# battery-charging.net
KiCad netlist of a schematic drawn in Altium Designer
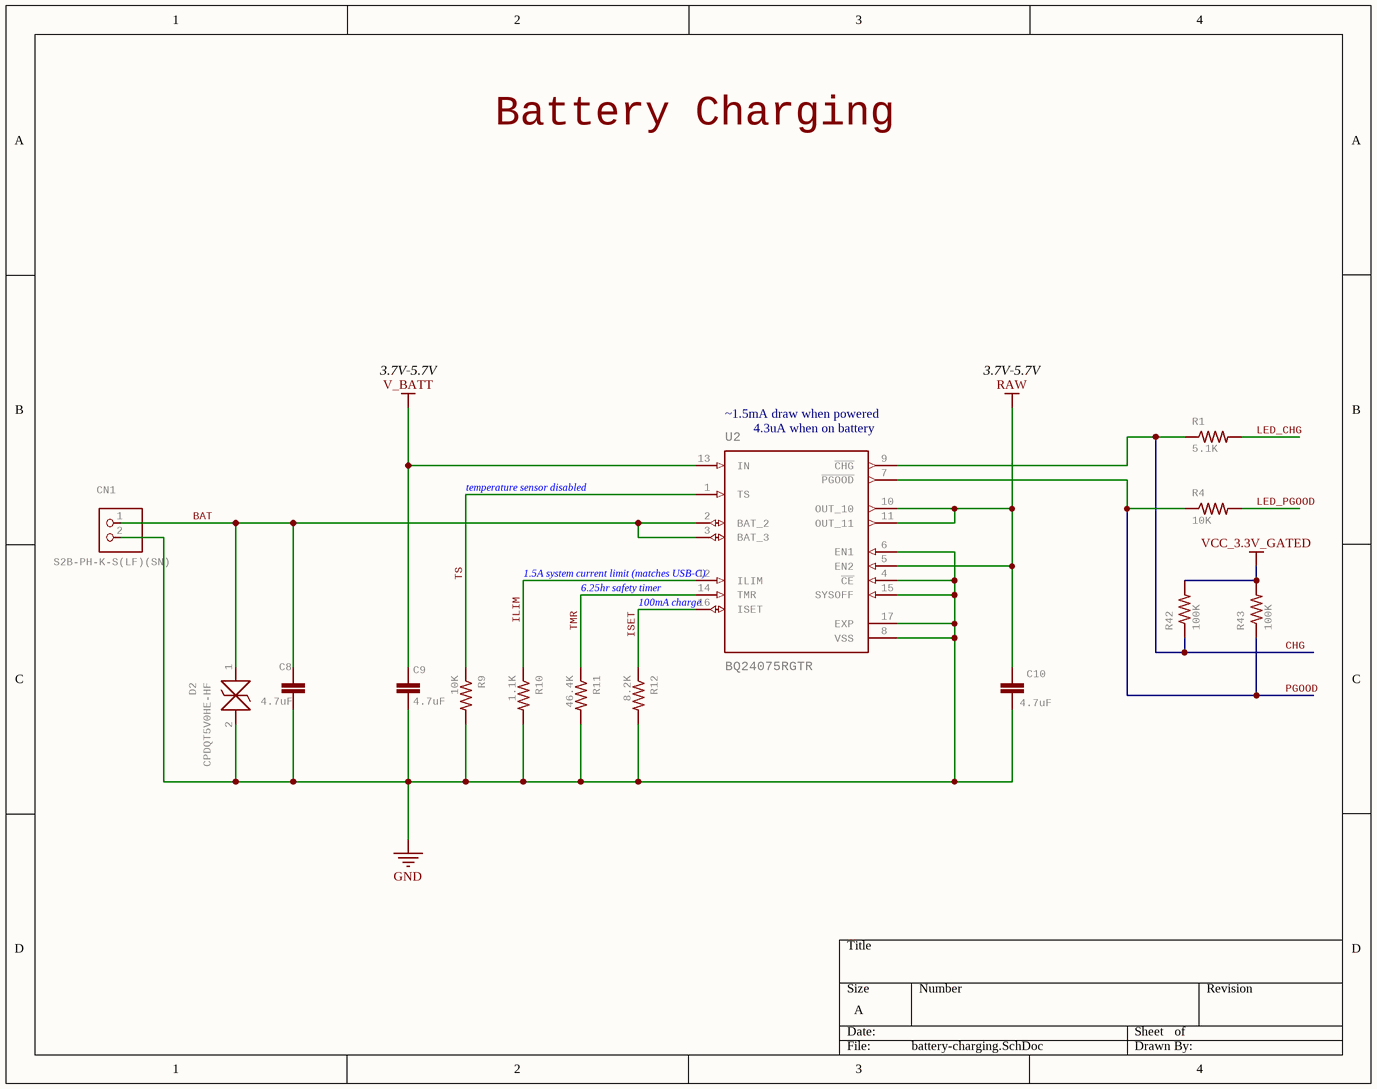
[diagram p0: battery-charging.SchDoc]

(export (version "E")
  (design (tool "Eeschema 10.0.6"))
  (components
    (comp (ref "C8")
      (value "4.7uF")
      (footprint "0402-CAP")
      (description "CapacitorStandard 0603 ceramic capacitor, and 0.1\" leaded capacitor.")
      (fields (field (name "MPN") "JMK105BBJ475MV-F"))
      (libsource (lib "rt10") (part "CAP0402-CAP"))
    )
    (comp (ref "C9")
      (value "4.7uF")
      (footprint "0402-CAP")
      (description "CapacitorStandard 0603 ceramic capacitor, and 0.1\" leaded capacitor.")
      (fields (field (name "MPN") "JMK105BBJ475MV-F"))
      (libsource (lib "rt10") (part "CAP0402-CAP"))
    )
    (comp (ref "C10")
      (value "4.7uF")
      (footprint "0402-CAP")
      (description "CapacitorStandard 0603 ceramic capacitor, and 0.1\" leaded capacitor.")
      (fields (field (name "MPN") "JMK105BBJ475MV-F"))
      (libsource (lib "rt10") (part "CAP0402-CAP"))
    )
    (comp (ref "CN1")
      (value "S2B-PH-K-S(LF)(SN)")
      (footprint "JST-PH-2-THM-RA")
      (fields (field (name "LIBRARYNAME") "adafruit-updated"))
      (libsource (lib "rt10") (part "JST_2PIN-THM-RA"))
    )
    (comp (ref "D2")
      (value "CPDQT5V0HE-HF")
      (footprint "CPDQT5V0HEHF")
      (description "ESD Suppressors / TVS Diodes DIODE ESD 5VWM 65W 0402/SOD-923F   Source:  Datasheet")
      (fields (field (name "MOUSER_PART_NUMBER") "MOUSER_PART_NUMBER"))
      (libsource (lib "rt10") (part "CPDQT5V0HE-HF"))
    )
    (comp (ref "R1")
      (value "5.1K")
      (footprint "0402-RES")
      (description "ResistorBasic schematic elements and footprints for 0603, 1206, and PTH resistors.")
      (fields (field (name "MPN") "RC0402JR-075K1L"))
      (libsource (lib "rt10") (part "RESISTOR0402-RES"))
    )
    (comp (ref "R4")
      (value "10K")
      (footprint "0402-RES")
      (description "ResistorBasic schematic elements and footprints for 0603, 1206, and PTH resistors.")
      (fields (field (name "MPN") "AC0402FR-1310KL"))
      (libsource (lib "rt10") (part "RESISTOR0402-RES"))
    )
    (comp (ref "R9")
      (value "10K")
      (footprint "0402-RES")
      (description "ResistorBasic schematic elements and footprints for 0603, 1206, and PTH resistors.")
      (fields (field (name "MPN") "AC0402FR-1310KL"))
      (libsource (lib "rt10") (part "RESISTOR0402-RES"))
    )
    (comp (ref "R10")
      (value "1.1K")
      (footprint "0402-RES")
      (description "ResistorBasic schematic elements and footprints for 0603, 1206, and PTH resistors.")
      (fields (field (name "MPN") "RC0402JR-071K1"))
      (libsource (lib "rt10") (part "RESISTOR0402-RES"))
    )
    (comp (ref "R11")
      (value "46.4K")
      (footprint "0402-RES")
      (description "ResistorBasic schematic elements and footprints for 0603, 1206, and PTH resistors.")
      (fields (field (name "MPN") "WR04X4642FTL"))
      (libsource (lib "rt10") (part "RESISTOR0402-RES"))
    )
    (comp (ref "R12")
      (value "8.2K")
      (footprint "0402-RES")
      (description "ResistorBasic schematic elements and footprints for 0603, 1206, and PTH resistors.")
      (fields (field (name "MPN") "CR0402-FX-8201GLF"))
      (libsource (lib "rt10") (part "RESISTOR0402-RES"))
    )
    (comp (ref "R42")
      (value "100K")
      (footprint "0402-RES")
      (description "ResistorBasic schematic elements and footprints for 0603, 1206, and PTH resistors.")
      (fields (field (name "MPN") "AC0402FR-07100KL"))
      (libsource (lib "rt10") (part "RESISTOR0402-RES"))
    )
    (comp (ref "R43")
      (value "100K")
      (footprint "0402-RES")
      (description "ResistorBasic schematic elements and footprints for 0603, 1206, and PTH resistors.")
      (fields (field (name "MPN") "AC0402FR-07100KL"))
      (libsource (lib "rt10") (part "RESISTOR0402-RES"))
    )
    (comp (ref "U2")
      (value "BQ24075RGTR")
      (footprint "QFN50P300X300X100-17N")
      (fields (field (name "MF") "Texas Instruments"))
      (libsource (lib "rt10") (part "BQ24075RGTR"))
    )
  )
  (nets
    (net (code "1") (name "/BAT") (class "Default")
      (node (ref "C8") (pin "2") (pinfunction "2_2") (pintype "passive"))
      (node (ref "CN1") (pin "1") (pinfunction "2_1") (pintype "passive"))
      (node (ref "D2") (pin "1") (pinfunction "1_1") (pintype "bidirectional"))
      (node (ref "U2") (pin "2") (pinfunction "BAT_2_2") (pintype "bidirectional"))
      (node (ref "U2") (pin "3") (pinfunction "BAT_3_3") (pintype "bidirectional"))
    )
    (net (code "2") (name "/CHG") (class "Default")
      (node (ref "R1") (pin "1") (pinfunction "1_1") (pintype "passive"))
      (node (ref "R42") (pin "1") (pinfunction "1_1") (pintype "passive"))
      (node (ref "U2") (pin "9") (pinfunction "~{CHG}_9") (pintype "output"))
    )
    (net (code "3") (name "/ILIM") (class "Default")
      (node (ref "R10") (pin "1") (pinfunction "1_1") (pintype "passive"))
      (node (ref "U2") (pin "12") (pinfunction "ILIM_12") (pintype "input"))
    )
    (net (code "4") (name "/ISET") (class "Default")
      (node (ref "R12") (pin "1") (pinfunction "1_1") (pintype "passive"))
      (node (ref "U2") (pin "16") (pinfunction "ISET_16") (pintype "bidirectional"))
    )
    (net (code "5") (name "/LED_CHG") (class "Default")
      (node (ref "R1") (pin "2") (pinfunction "2_2") (pintype "passive"))
    )
    (net (code "6") (name "/LED_PGOOD") (class "Default")
      (node (ref "R4") (pin "2") (pinfunction "2_2") (pintype "passive"))
    )
    (net (code "7") (name "/PGOOD") (class "Default")
      (node (ref "R4") (pin "1") (pinfunction "1_1") (pintype "passive"))
      (node (ref "R43") (pin "1") (pinfunction "1_1") (pintype "passive"))
      (node (ref "U2") (pin "7") (pinfunction "~{PGOOD}_7") (pintype "output"))
    )
    (net (code "8") (name "/TMR") (class "Default")
      (node (ref "R11") (pin "1") (pinfunction "1_1") (pintype "passive"))
      (node (ref "U2") (pin "14") (pinfunction "TMR_14") (pintype "input"))
    )
    (net (code "9") (name "/TS") (class "Default")
      (node (ref "R9") (pin "1") (pinfunction "1_1") (pintype "passive"))
      (node (ref "U2") (pin "1") (pinfunction "TS_1") (pintype "input"))
    )
    (net (code "10") (name "GND") (class "Default")
      (node (ref "C10") (pin "1") (pinfunction "1_1") (pintype "passive"))
      (node (ref "C8") (pin "1") (pinfunction "1_1") (pintype "passive"))
      (node (ref "C9") (pin "1") (pinfunction "1_1") (pintype "passive"))
      (node (ref "CN1") (pin "2") (pinfunction "1_2") (pintype "passive"))
      (node (ref "D2") (pin "2") (pinfunction "2_2") (pintype "bidirectional"))
      (node (ref "R10") (pin "2") (pinfunction "2_2") (pintype "passive"))
      (node (ref "R11") (pin "2") (pinfunction "2_2") (pintype "passive"))
      (node (ref "R12") (pin "2") (pinfunction "2_2") (pintype "passive"))
      (node (ref "R9") (pin "2") (pinfunction "2_2") (pintype "passive"))
      (node (ref "U2") (pin "15") (pinfunction "SYSOFF_15") (pintype "input"))
      (node (ref "U2") (pin "17") (pinfunction "EXP_17") (pintype "power_in"))
      (node (ref "U2") (pin "4") (pinfunction "~{CE}_4") (pintype "input"))
      (node (ref "U2") (pin "6") (pinfunction "EN1_6") (pintype "input"))
      (node (ref "U2") (pin "8") (pinfunction "VSS_8") (pintype "power_in"))
    )
    (net (code "11") (name "RAW") (class "Default")
      (node (ref "C10") (pin "2") (pinfunction "2_2") (pintype "passive"))
      (node (ref "U2") (pin "10") (pinfunction "OUT_10_10") (pintype "output"))
      (node (ref "U2") (pin "11") (pinfunction "OUT_11_11") (pintype "output"))
      (node (ref "U2") (pin "5") (pinfunction "EN2_5") (pintype "input"))
    )
    (net (code "12") (name "VCC_3.3V_GATED") (class "Default")
      (node (ref "R42") (pin "2") (pinfunction "2_2") (pintype "passive"))
      (node (ref "R43") (pin "2") (pinfunction "2_2") (pintype "passive"))
    )
    (net (code "13") (name "V_BATT") (class "Default")
      (node (ref "C9") (pin "2") (pinfunction "2_2") (pintype "passive"))
      (node (ref "U2") (pin "13") (pinfunction "IN_13") (pintype "input"))
    )
  )
)
